# IMU9.net
KiCad netlist of a schematic drawn in EAGLE
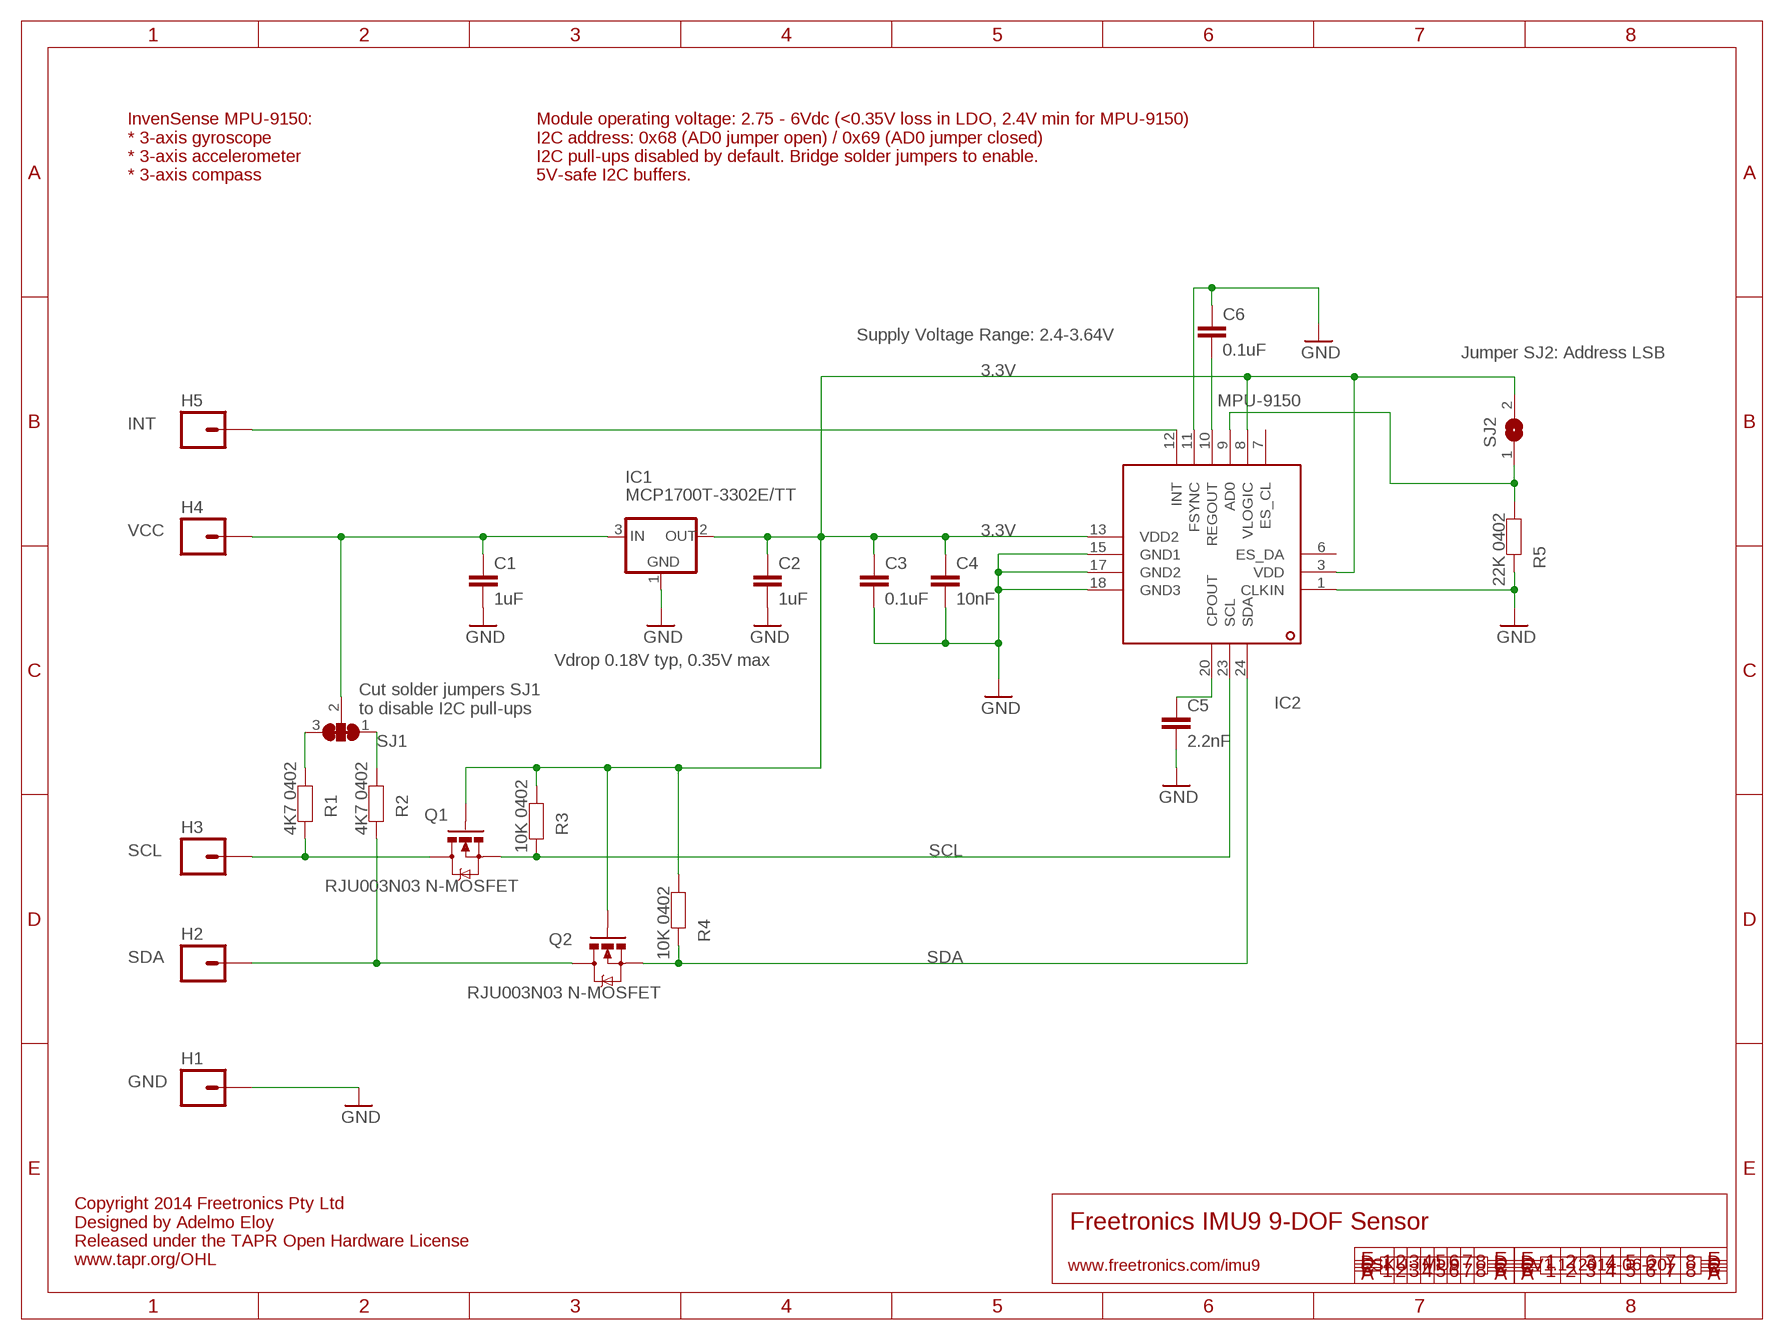
[diagram p0: schematic, sheet 1]

(export (version "E")
  (design (tool "Eeschema 10.0.6"))
  (components
    (comp (ref "C1")
      (value "1uF")
      (footprint "eagle-import:0603")
      (libsource (lib "eagle-import") (part "CAP0603"))
    )
    (comp (ref "C2")
      (value "1uF")
      (footprint "eagle-import:0603")
      (libsource (lib "eagle-import") (part "CAP0603"))
    )
    (comp (ref "C3")
      (value "0.1uF")
      (footprint "eagle-import:0603")
      (libsource (lib "eagle-import") (part "CAP0603"))
    )
    (comp (ref "C4")
      (value "10nF")
      (footprint "eagle-import:0603")
      (libsource (lib "eagle-import") (part "CAP0603"))
    )
    (comp (ref "C5")
      (value "2.2nF")
      (footprint "eagle-import:0603")
      (libsource (lib "eagle-import") (part "CAP0603"))
    )
    (comp (ref "C6")
      (value "0.1uF")
      (footprint "eagle-import:0603")
      (libsource (lib "eagle-import") (part "CAP0603"))
    )
    (comp (ref "H1")
      (value "GND")
      (footprint "eagle-import:1X01")
      (libsource (lib "eagle-import") (part "M01PTH"))
    )
    (comp (ref "H2")
      (value "SDA")
      (footprint "eagle-import:1X01")
      (libsource (lib "eagle-import") (part "M01PTH"))
    )
    (comp (ref "H3")
      (value "SCL")
      (footprint "eagle-import:1X01")
      (libsource (lib "eagle-import") (part "M01PTH"))
    )
    (comp (ref "H4")
      (value "VCC")
      (footprint "eagle-import:1X01")
      (libsource (lib "eagle-import") (part "M01PTH"))
    )
    (comp (ref "H5")
      (value "INT")
      (footprint "eagle-import:1X01")
      (libsource (lib "eagle-import") (part "M01PTH"))
    )
    (comp (ref "IC1")
      (value "MCP1700T-3302E/TT")
      (footprint "eagle-import:SOT23-3")
      (libsource (lib "eagle-import") (part "V_REG_78XXSOT23-3"))
    )
    (comp (ref "IC2")
      (value "MPU-9150")
      (footprint "eagle-import:QFN-24MPU")
      (libsource (lib "eagle-import") (part "MPU-9150"))
    )
    (comp (ref "Q1")
      (value "RJU003N03 N-MOSFET")
      (footprint "eagle-import:SOT32-3")
      (libsource (lib "eagle-import") (part "MOSFET-NSOT-323"))
    )
    (comp (ref "Q2")
      (value "RJU003N03 N-MOSFET")
      (footprint "eagle-import:SOT32-3")
      (libsource (lib "eagle-import") (part "MOSFET-NSOT-323"))
    )
    (comp (ref "R1")
      (value "4K7 0402")
      (footprint "eagle-import:0402")
      (libsource (lib "eagle-import") (part "RESISTOR0402"))
    )
    (comp (ref "R2")
      (value "4K7 0402")
      (footprint "eagle-import:0402")
      (libsource (lib "eagle-import") (part "RESISTOR0402"))
    )
    (comp (ref "R3")
      (value "10K 0402")
      (footprint "eagle-import:0402")
      (libsource (lib "eagle-import") (part "RESISTOR0402"))
    )
    (comp (ref "R4")
      (value "10K 0402")
      (footprint "eagle-import:0402")
      (libsource (lib "eagle-import") (part "RESISTOR0402"))
    )
    (comp (ref "R5")
      (value "22K 0402")
      (footprint "eagle-import:0402")
      (libsource (lib "eagle-import") (part "RESISTOR0402"))
    )
    (comp (ref "SJ1")
      (value "SJ2W")
      (footprint "eagle-import:SJ_2")
      (libsource (lib "eagle-import") (part "SJ2W"))
    )
    (comp (ref "SJ2") (value "SJ") (footprint "eagle-import:SJ") (libsource (lib "eagle-import") (part "SJ")))
  )
  (nets
    (net (code "1") (name "/3.3V") (class "Default")
      (node (ref "C2") (pin "1") (pinfunction "1_1") (pintype "passive"))
      (node (ref "C3") (pin "1") (pinfunction "1_1") (pintype "passive"))
      (node (ref "C4") (pin "1") (pinfunction "1_1") (pintype "passive"))
      (node (ref "IC1") (pin "2") (pinfunction "OUT_2") (pintype "output"))
      (node (ref "IC2") (pin "13") (pinfunction "VDD2_13") (pintype "bidirectional"))
      (node (ref "IC2") (pin "3") (pinfunction "VDD_3") (pintype "bidirectional"))
      (node (ref "IC2") (pin "8") (pinfunction "VLOGIC_8") (pintype "bidirectional"))
      (node (ref "Q1") (pin "1") (pinfunction "G_1") (pintype "passive"))
      (node (ref "Q2") (pin "1") (pinfunction "G_1") (pintype "passive"))
      (node (ref "R3") (pin "2") (pinfunction "2_2") (pintype "passive"))
      (node (ref "R4") (pin "2") (pinfunction "2_2") (pintype "passive"))
      (node (ref "SJ2") (pin "2") (pinfunction "2_2") (pintype "passive"))
    )
    (net (code "2") (name "/SCL") (class "Default")
      (node (ref "H3") (pin "1") (pinfunction "1_1") (pintype "passive"))
      (node (ref "Q1") (pin "3") (pinfunction "D_3") (pintype "passive"))
      (node (ref "R1") (pin "1") (pinfunction "1_1") (pintype "passive"))
    )
    (net (code "3") (name "/SDA") (class "Default")
      (node (ref "H2") (pin "1") (pinfunction "1_1") (pintype "passive"))
      (node (ref "Q2") (pin "3") (pinfunction "D_3") (pintype "passive"))
      (node (ref "R2") (pin "1") (pinfunction "1_1") (pintype "passive"))
    )
    (net (code "4") (name "GND") (class "Default")
      (node (ref "C1") (pin "2") (pinfunction "2_2") (pintype "passive"))
      (node (ref "C2") (pin "2") (pinfunction "2_2") (pintype "passive"))
      (node (ref "C3") (pin "2") (pinfunction "2_2") (pintype "passive"))
      (node (ref "C4") (pin "2") (pinfunction "2_2") (pintype "passive"))
      (node (ref "C5") (pin "2") (pinfunction "2_2") (pintype "passive"))
      (node (ref "C6") (pin "1") (pinfunction "1_1") (pintype "passive"))
      (node (ref "H1") (pin "1") (pinfunction "1_1") (pintype "passive"))
      (node (ref "IC1") (pin "1") (pinfunction "GND_1") (pintype "input"))
      (node (ref "IC2") (pin "1") (pinfunction "CLKIN_1") (pintype "bidirectional"))
      (node (ref "IC2") (pin "11") (pinfunction "FSYNC_11") (pintype "bidirectional"))
      (node (ref "IC2") (pin "15") (pinfunction "GND1_15") (pintype "bidirectional"))
      (node (ref "IC2") (pin "17") (pinfunction "GND2_17") (pintype "bidirectional"))
      (node (ref "IC2") (pin "18") (pinfunction "GND3_18") (pintype "bidirectional"))
      (node (ref "R5") (pin "1") (pinfunction "1_1") (pintype "passive"))
    )
    (net (code "5") (name "Net-(IC1-IN)") (class "Default")
      (node (ref "C1") (pin "1") (pinfunction "1_1") (pintype "passive"))
      (node (ref "H4") (pin "1") (pinfunction "1_1") (pintype "passive"))
      (node (ref "IC1") (pin "3") (pinfunction "IN_3") (pintype "input"))
      (node (ref "SJ1") (pin "2") (pinfunction "2_2") (pintype "passive"))
    )
    (net (code "6") (name "Net-(IC2-AD0)") (class "Default")
      (node (ref "IC2") (pin "9") (pinfunction "AD0_9") (pintype "bidirectional"))
      (node (ref "R5") (pin "2") (pinfunction "2_2") (pintype "passive"))
      (node (ref "SJ2") (pin "1") (pinfunction "1_1") (pintype "passive"))
    )
    (net (code "7") (name "Net-(IC2-CPOUT)") (class "Default")
      (node (ref "C5") (pin "1") (pinfunction "1_1") (pintype "passive"))
      (node (ref "IC2") (pin "20") (pinfunction "CPOUT_20") (pintype "bidirectional"))
    )
    (net (code "8") (name "Net-(IC2-INT)") (class "Default")
      (node (ref "H5") (pin "1") (pinfunction "1_1") (pintype "passive"))
      (node (ref "IC2") (pin "12") (pinfunction "INT_12") (pintype "bidirectional"))
    )
    (net (code "9") (name "Net-(IC2-REGOUT)") (class "Default")
      (node (ref "C6") (pin "2") (pinfunction "2_2") (pintype "passive"))
      (node (ref "IC2") (pin "10") (pinfunction "REGOUT_10") (pintype "bidirectional"))
    )
    (net (code "10") (name "Net-(IC2-SCL)") (class "Default")
      (node (ref "IC2") (pin "23") (pinfunction "SCL_23") (pintype "bidirectional"))
      (node (ref "Q1") (pin "2") (pinfunction "S_2") (pintype "passive"))
      (node (ref "R3") (pin "1") (pinfunction "1_1") (pintype "passive"))
    )
    (net (code "11") (name "Net-(IC2-SDA)") (class "Default")
      (node (ref "IC2") (pin "24") (pinfunction "SDA_24") (pintype "bidirectional"))
      (node (ref "Q2") (pin "2") (pinfunction "S_2") (pintype "passive"))
      (node (ref "R4") (pin "1") (pinfunction "1_1") (pintype "passive"))
    )
    (net (code "12") (name "Net-(R1-Pad2)") (class "Default")
      (node (ref "R1") (pin "2") (pinfunction "2_2") (pintype "passive"))
      (node (ref "SJ1") (pin "3") (pinfunction "3_3") (pintype "passive"))
    )
    (net (code "13") (name "Net-(R2-Pad2)") (class "Default")
      (node (ref "R2") (pin "2") (pinfunction "2_2") (pintype "passive"))
      (node (ref "SJ1") (pin "1") (pinfunction "1_1") (pintype "passive"))
    )
    (net (code "14") (name "unconnected-(IC2-ES_CL-Pad7)") (class "Default")
      (node (ref "IC2") (pin "7") (pinfunction "ES_CL_7") (pintype "bidirectional"))
    )
    (net (code "15") (name "unconnected-(IC2-ES_DA-Pad6)") (class "Default")
      (node (ref "IC2") (pin "6") (pinfunction "ES_DA_6") (pintype "bidirectional"))
    )
  )
)
